# power_Exodia.net
KiCad netlist of a schematic drawn in EAGLE
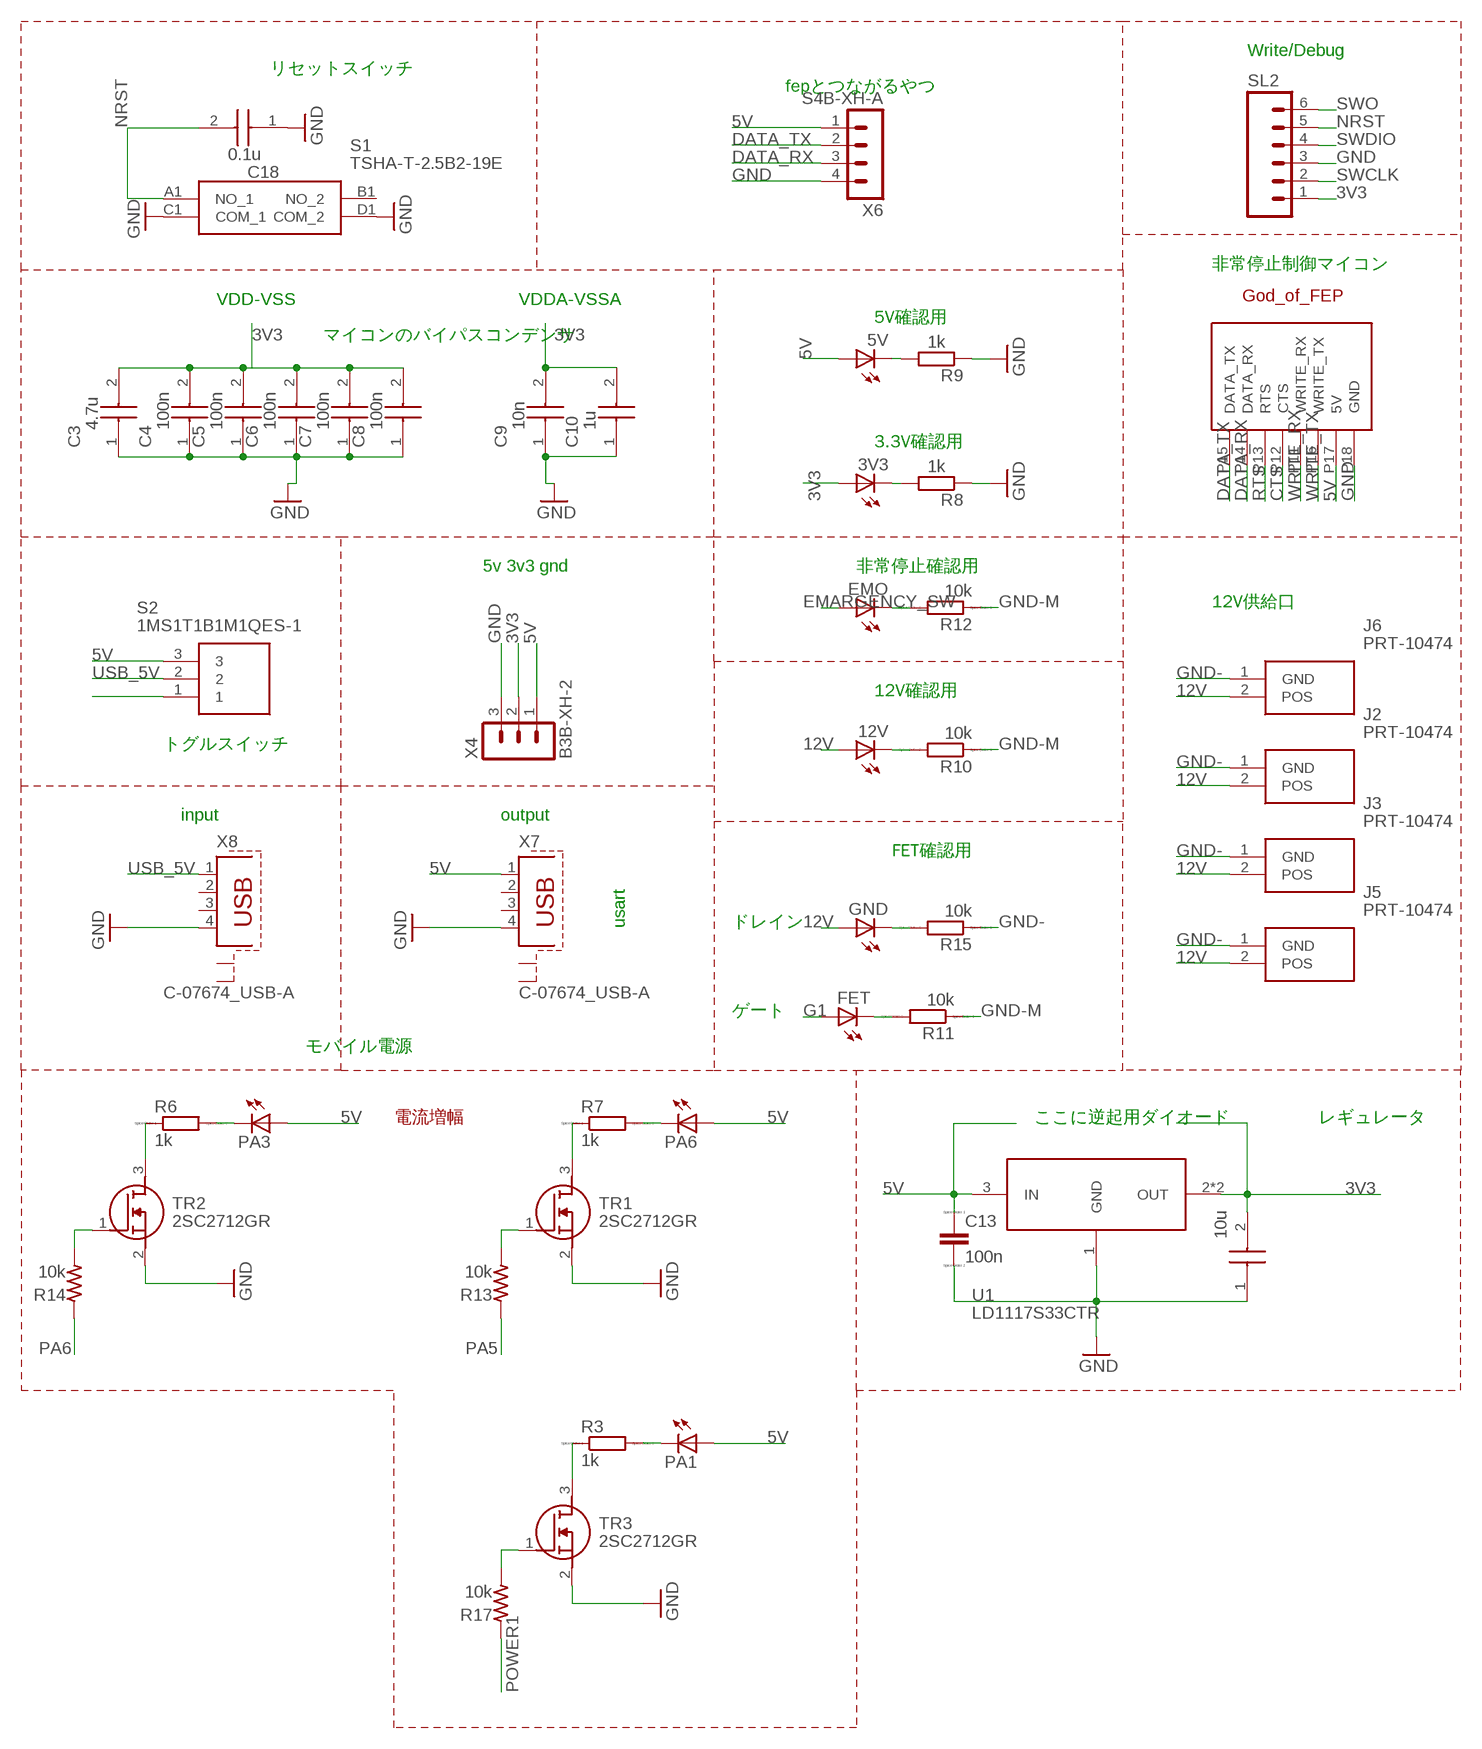
[diagram p0: schematic, sheet 1]
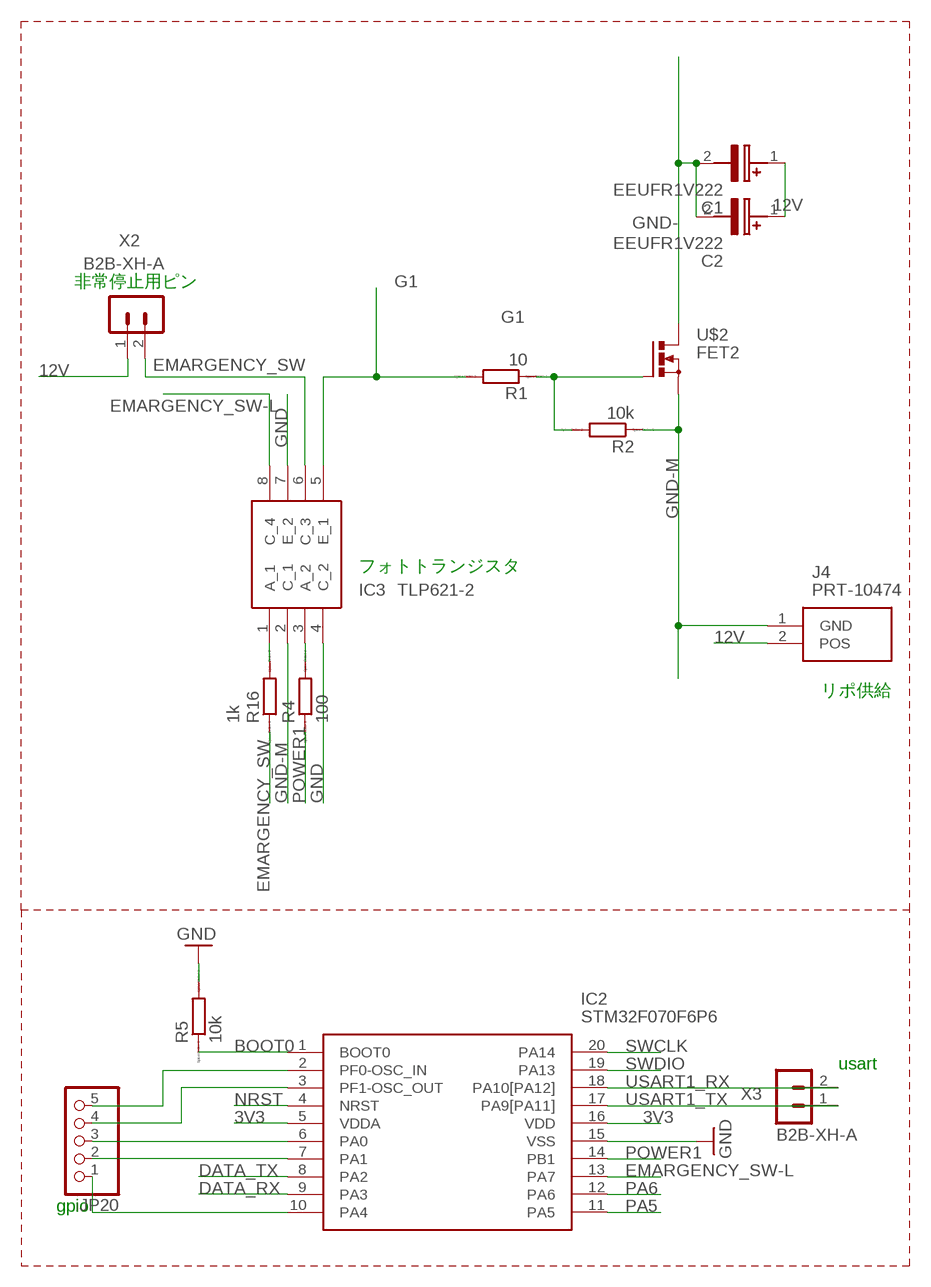
[diagram p1: schematic, sheet 2]

(export (version "E")
  (design (tool "Eeschema 10.0.6"))
  (components
    (comp (ref "3V3")
      (value "LED3MM")
      (footprint "eagle-import:LED3MM")
      (libsource (lib "eagle-import") (part "LED3MM"))
    )
    (comp (ref "5V")
      (value "LED3MM")
      (footprint "eagle-import:LED3MM")
      (libsource (lib "eagle-import") (part "LED3MM"))
    )
    (comp (ref "10U")
      (value "10u")
      (footprint "eagle-import:CAPC1608X90N")
      (fields
        (field (name "MANUFACTURER_PART_NUMBER") "GRM188B31A106KE69D")
        (field (name "RS_PART_NUMBER") "8847157P")
      )
      (libsource (lib "eagle-import") (part "GRM188B31A106KE69D"))
    )
    (comp (ref "12V")
      (value "LED3MM")
      (footprint "eagle-import:LED3MM")
      (libsource (lib "eagle-import") (part "LED3MM"))
    )
    (comp (ref "C3")
      (value "4.7u")
      (footprint "eagle-import:CAPC1709X100N")
      (fields
        (field (name "MANUFACTURER_PART_NUMBER") "AMK107BBJ476MA-RE")
        (field (name "MOUSER_PART_NUMBER") "963-AMK107BBJ476MARE")
        (field (name "RS_PART_NUMBER") "1843762P")
      )
      (libsource (lib "eagle-import") (part "AMK107BBJ476MA-RE"))
    )
    (comp (ref "C4")
      (value "100n")
      (footprint "eagle-import:CAPC1709X100N")
      (fields
        (field (name "MANUFACTURER_PART_NUMBER") "AMK107BBJ476MA-RE")
        (field (name "MOUSER_PART_NUMBER") "963-AMK107BBJ476MARE")
        (field (name "RS_PART_NUMBER") "1843762P")
      )
      (libsource (lib "eagle-import") (part "AMK107BBJ476MA-RE"))
    )
    (comp (ref "C5")
      (value "100n")
      (footprint "eagle-import:CAPC1709X100N")
      (fields
        (field (name "MANUFACTURER_PART_NUMBER") "AMK107BBJ476MA-RE")
        (field (name "MOUSER_PART_NUMBER") "963-AMK107BBJ476MARE")
        (field (name "RS_PART_NUMBER") "1843762P")
      )
      (libsource (lib "eagle-import") (part "AMK107BBJ476MA-RE"))
    )
    (comp (ref "C6")
      (value "100n")
      (footprint "eagle-import:CAPC1709X100N")
      (fields
        (field (name "MANUFACTURER_PART_NUMBER") "AMK107BBJ476MA-RE")
        (field (name "MOUSER_PART_NUMBER") "963-AMK107BBJ476MARE")
        (field (name "RS_PART_NUMBER") "1843762P")
      )
      (libsource (lib "eagle-import") (part "AMK107BBJ476MA-RE"))
    )
    (comp (ref "C7")
      (value "100n")
      (footprint "eagle-import:CAPC1709X100N")
      (fields
        (field (name "MANUFACTURER_PART_NUMBER") "AMK107BBJ476MA-RE")
        (field (name "MOUSER_PART_NUMBER") "963-AMK107BBJ476MARE")
        (field (name "RS_PART_NUMBER") "1843762P")
      )
      (libsource (lib "eagle-import") (part "AMK107BBJ476MA-RE"))
    )
    (comp (ref "C8")
      (value "100n")
      (footprint "eagle-import:CAPC1709X100N")
      (fields
        (field (name "MANUFACTURER_PART_NUMBER") "AMK107BBJ476MA-RE")
        (field (name "MOUSER_PART_NUMBER") "963-AMK107BBJ476MARE")
        (field (name "RS_PART_NUMBER") "1843762P")
      )
      (libsource (lib "eagle-import") (part "AMK107BBJ476MA-RE"))
    )
    (comp (ref "C9")
      (value "10n")
      (footprint "eagle-import:CAPC1709X100N")
      (fields
        (field (name "MANUFACTURER_PART_NUMBER") "AMK107BBJ476MA-RE")
        (field (name "MOUSER_PART_NUMBER") "963-AMK107BBJ476MARE")
        (field (name "RS_PART_NUMBER") "1843762P")
      )
      (libsource (lib "eagle-import") (part "AMK107BBJ476MA-RE"))
    )
    (comp (ref "C10")
      (value "1u")
      (footprint "eagle-import:CAPC1709X100N")
      (fields
        (field (name "MANUFACTURER_PART_NUMBER") "AMK107BBJ476MA-RE")
        (field (name "MOUSER_PART_NUMBER") "963-AMK107BBJ476MARE")
        (field (name "RS_PART_NUMBER") "1843762P")
      )
      (libsource (lib "eagle-import") (part "AMK107BBJ476MA-RE"))
    )
    (comp (ref "C13")
      (value "100n")
      (footprint "eagle-import:C1608")
      (libsource (lib "eagle-import") (part "CC1608"))
    )
    (comp (ref "C18")
      (value "0.1u")
      (footprint "eagle-import:CAPC1709X100N")
      (fields
        (field (name "MANUFACTURER_PART_NUMBER") "AMK107BBJ476MA-RE")
        (field (name "MOUSER_PART_NUMBER") "963-AMK107BBJ476MARE")
        (field (name "RS_PART_NUMBER") "1843762P")
      )
      (libsource (lib "eagle-import") (part "AMK107BBJ476MA-RE"))
    )
    (comp (ref "EMO")
      (value "LED3MM")
      (footprint "eagle-import:LED3MM")
      (libsource (lib "eagle-import") (part "LED3MM"))
    )
    (comp (ref "FEP_2")
      (value "GOD_OF_FEP")
      (footprint "eagle-import:GOD_OF_FEP")
      (libsource (lib "eagle-import") (part "GOD_OF_FEP"))
    )
    (comp (ref "FET")
      (value "LED3MM")
      (footprint "eagle-import:LED3MM")
      (libsource (lib "eagle-import") (part "LED3MM"))
    )
    (comp (ref "GND")
      (value "LED3MM")
      (footprint "eagle-import:LED3MM")
      (libsource (lib "eagle-import") (part "LED3MM"))
    )
    (comp (ref "J2")
      (value "PRT-10474")
      (footprint "eagle-import:SHDR2W320P716_1X2_1574X813X158")
      (fields (field (name "MOUSER_PART_NUMBER") "474-PRT-10474"))
      (libsource (lib "eagle-import") (part "PRT-10474"))
    )
    (comp (ref "J3")
      (value "PRT-10474")
      (footprint "eagle-import:SHDR2W320P716_1X2_1574X813X158")
      (fields (field (name "MOUSER_PART_NUMBER") "474-PRT-10474"))
      (libsource (lib "eagle-import") (part "PRT-10474"))
    )
    (comp (ref "J5")
      (value "PRT-10474")
      (footprint "eagle-import:SHDR2W320P716_1X2_1574X813X158")
      (fields (field (name "MOUSER_PART_NUMBER") "474-PRT-10474"))
      (libsource (lib "eagle-import") (part "PRT-10474"))
    )
    (comp (ref "J6")
      (value "PRT-10474")
      (footprint "eagle-import:SHDR2W320P716_1X2_1574X813X158")
      (fields (field (name "MOUSER_PART_NUMBER") "474-PRT-10474"))
      (libsource (lib "eagle-import") (part "PRT-10474"))
    )
    (comp (ref "PA1")
      (value "LED3MM")
      (footprint "eagle-import:LED3MM")
      (libsource (lib "eagle-import") (part "LED3MM"))
    )
    (comp (ref "PA3")
      (value "LED3MM")
      (footprint "eagle-import:LED3MM")
      (libsource (lib "eagle-import") (part "LED3MM"))
    )
    (comp (ref "PA6")
      (value "LED3MM")
      (footprint "eagle-import:LED3MM")
      (libsource (lib "eagle-import") (part "LED3MM"))
    )
    (comp (ref "R3")
      (value "1k")
      (footprint "eagle-import:R0603")
      (libsource (lib "eagle-import") (part "RR0603"))
    )
    (comp (ref "R6")
      (value "1k")
      (footprint "eagle-import:R0603")
      (libsource (lib "eagle-import") (part "RR0603"))
    )
    (comp (ref "R7")
      (value "1k")
      (footprint "eagle-import:R0603")
      (libsource (lib "eagle-import") (part "RR0603"))
    )
    (comp (ref "R8")
      (value "1k")
      (footprint "eagle-import:1608")
      (libsource (lib "eagle-import") (part "R1608"))
    )
    (comp (ref "R9")
      (value "1k")
      (footprint "eagle-import:1608")
      (libsource (lib "eagle-import") (part "R1608"))
    )
    (comp (ref "R10")
      (value "10k")
      (footprint "eagle-import:R0603")
      (libsource (lib "eagle-import") (part "RR0603"))
    )
    (comp (ref "R11")
      (value "10k")
      (footprint "eagle-import:R0603")
      (libsource (lib "eagle-import") (part "RR0603"))
    )
    (comp (ref "R12")
      (value "10k")
      (footprint "eagle-import:R0603")
      (libsource (lib "eagle-import") (part "RR0603"))
    )
    (comp (ref "R13")
      (value "10k")
      (footprint "eagle-import:SMD1608")
      (libsource (lib "eagle-import") (part "RESISTOR-US1608"))
    )
    (comp (ref "R14")
      (value "10k")
      (footprint "eagle-import:SMD1608")
      (libsource (lib "eagle-import") (part "RESISTOR-US1608"))
    )
    (comp (ref "R15")
      (value "10k")
      (footprint "eagle-import:R0603")
      (libsource (lib "eagle-import") (part "RR0603"))
    )
    (comp (ref "R17")
      (value "10k")
      (footprint "eagle-import:SMD1608")
      (libsource (lib "eagle-import") (part "RESISTOR-US1608"))
    )
    (comp (ref "S1")
      (value "TSHA-T-2.5B2-19E")
      (footprint "eagle-import:TSHAT25B219E")
      (libsource (lib "eagle-import") (part "TSHA-T-2.5B2-19E"))
    )
    (comp (ref "S2")
      (value "1MS1T1B1M1QES-1")
      (footprint "eagle-import:1MS1T1B1M1QES-1")
      (libsource (lib "eagle-import") (part "1MS1T1B1M1QES-1"))
    )
    (comp (ref "SL2")
      (value "MA06")
      (footprint "eagle-import:06PA")
      (libsource (lib "eagle-import") (part "MA06"))
    )
    (comp (ref "TR1")
      (value "2SC2712GR")
      (footprint "eagle-import:SOT-23")
      (libsource (lib "eagle-import") (part "SOT-23_NMOS"))
    )
    (comp (ref "TR2")
      (value "2SC2712GR")
      (footprint "eagle-import:SOT-23")
      (libsource (lib "eagle-import") (part "SOT-23_NMOS"))
    )
    (comp (ref "TR3")
      (value "2SC2712GR")
      (footprint "eagle-import:SOT-23")
      (libsource (lib "eagle-import") (part "SOT-23_NMOS"))
    )
    (comp (ref "U1")
      (value "LD1117S33CTR")
      (footprint "eagle-import:SOT223")
      (fields (field (name "MF") "STMicroelectronics"))
      (libsource (lib "eagle-import") (part "LD1117S33CTR"))
    )
    (comp (ref "X4")
      (value "B3B-XH-2")
      (footprint "eagle-import:B3B-XH-A")
      (libsource (lib "eagle-import") (part "B3B-XH-2"))
    )
    (comp (ref "X6")
      (value "S4B-XH-A")
      (footprint "eagle-import:S4B-XH-A")
      (libsource (lib "eagle-import") (part "S4B-XH-A"))
    )
    (comp (ref "X7")
      (value "C-07674_USB-A")
      (footprint "eagle-import:PN87520-S")
      (libsource (lib "eagle-import") (part "C-07674_USB-A"))
    )
    (comp (ref "X8")
      (value "C-07674_USB-A")
      (footprint "eagle-import:PN87520-S")
      (libsource (lib "eagle-import") (part "C-07674_USB-A"))
    )
    (comp (ref "C1")
      (value "EEUFR1V222")
      (footprint "eagle-import:CAPPRD750W85D1600H2700")
      (libsource (lib "eagle-import") (part "EEUFR1V222"))
    )
    (comp (ref "C2")
      (value "EEUFR1V222")
      (footprint "eagle-import:CAPPRD750W85D1600H2700")
      (libsource (lib "eagle-import") (part "EEUFR1V222"))
    )
    (comp (ref "IC2")
      (value "STM32F070F6P6")
      (footprint "eagle-import:SOP65P640X120-20N")
      (fields (field (name "MOUSER_PART_NUMBER") "511-STM32F070F6P6"))
      (libsource (lib "eagle-import") (part "STM32F070F6P6"))
    )
    (comp (ref "IC3")
      (value "TLP621-2")
      (footprint "eagle-import:DIP762W60P254L966H485Q8N")
      (fields (field (name "MOUSER_PART_NUMBER") "757-TLP621-2"))
      (libsource (lib "eagle-import") (part "TLP621-2"))
    )
    (comp (ref "J4")
      (value "PRT-10474")
      (footprint "eagle-import:SHDR2W320P716_1X2_1574X813X158")
      (fields (field (name "MOUSER_PART_NUMBER") "474-PRT-10474"))
      (libsource (lib "eagle-import") (part "PRT-10474"))
    )
    (comp (ref "JP20")
      (value "PINHD-1X5")
      (footprint "eagle-import:1X05")
      (libsource (lib "eagle-import") (part "PINHD-1X5"))
    )
    (comp (ref "R1")
      (value "10")
      (footprint "eagle-import:R0603")
      (libsource (lib "eagle-import") (part "RR0603"))
    )
    (comp (ref "R2")
      (value "10k")
      (footprint "eagle-import:R0603")
      (libsource (lib "eagle-import") (part "RR0603"))
    )
    (comp (ref "R4")
      (value "100")
      (footprint "eagle-import:R0603")
      (libsource (lib "eagle-import") (part "RR0603"))
    )
    (comp (ref "R5")
      (value "10k")
      (footprint "eagle-import:R0603")
      (libsource (lib "eagle-import") (part "RR0603"))
    )
    (comp (ref "R16")
      (value "1k")
      (footprint "eagle-import:R0603")
      (libsource (lib "eagle-import") (part "RR0603"))
    )
    (comp (ref "U$2")
      (value "FET2")
      (footprint "eagle-import:FET2")
      (libsource (lib "eagle-import") (part "FET2"))
    )
    (comp (ref "X2")
      (value "B2B-XH-A")
      (footprint "eagle-import:B2B-XH-A")
      (libsource (lib "eagle-import") (part "B2B-XH-A"))
    )
    (comp (ref "X3")
      (value "B2B-XH-A")
      (footprint "eagle-import:B2B-XH-A")
      (libsource (lib "eagle-import") (part "B2B-XH-A"))
    )
  )
  (nets
    (net (code "1") (name "3V3") (class "Default")
      (node (ref "10U") (pin "2") (pinfunction "2_2") (pintype "bidirectional"))
      (node (ref "3V3") (pin "A") (pinfunction "A_A") (pintype "passive"))
      (node (ref "C10") (pin "2") (pinfunction "2_2") (pintype "bidirectional"))
      (node (ref "C3") (pin "2") (pinfunction "2_2") (pintype "bidirectional"))
      (node (ref "C4") (pin "2") (pinfunction "2_2") (pintype "bidirectional"))
      (node (ref "C5") (pin "2") (pinfunction "2_2") (pintype "bidirectional"))
      (node (ref "C6") (pin "2") (pinfunction "2_2") (pintype "bidirectional"))
      (node (ref "C7") (pin "2") (pinfunction "2_2") (pintype "bidirectional"))
      (node (ref "C8") (pin "2") (pinfunction "2_2") (pintype "bidirectional"))
      (node (ref "C9") (pin "2") (pinfunction "2_2") (pintype "bidirectional"))
      (node (ref "IC2") (pin "16") (pinfunction "VDD_16") (pintype "bidirectional"))
      (node (ref "IC2") (pin "5") (pinfunction "VDDA_5") (pintype "bidirectional"))
      (node (ref "SL2") (pin "1") (pinfunction "1_1") (pintype "passive"))
      (node (ref "U1") (pin "2") (pinfunction "OUT_2") (pintype "output"))
      (node (ref "U1") (pin "4") (pinfunction "OUT_4") (pintype "output"))
      (node (ref "X4") (pin "2") (pinfunction "2_2") (pintype "passive"))
    )
    (net (code "2") (name "5V") (class "Default")
      (node (ref "5V") (pin "A") (pinfunction "A_A") (pintype "passive"))
      (node (ref "C13") (pin "1") (pinfunction "1_1") (pintype "passive"))
      (node (ref "FEP_2") (pin "P17") (pinfunction "5V_P17") (pintype "bidirectional"))
      (node (ref "PA1") (pin "A") (pinfunction "A_A") (pintype "passive"))
      (node (ref "PA3") (pin "A") (pinfunction "A_A") (pintype "passive"))
      (node (ref "PA6") (pin "A") (pinfunction "A_A") (pintype "passive"))
      (node (ref "S2") (pin "3") (pinfunction "3_3") (pintype "bidirectional"))
      (node (ref "U1") (pin "3") (pinfunction "IN_3") (pintype "input"))
      (node (ref "X4") (pin "1") (pinfunction "1_1") (pintype "passive"))
      (node (ref "X6") (pin "1") (pinfunction "1_1") (pintype "passive"))
      (node (ref "X7") (pin "1") (pinfunction "1_1") (pintype "passive"))
    )
    (net (code "3") (name "12V") (class "Default")
      (node (ref "12V") (pin "A") (pinfunction "A_A") (pintype "passive"))
      (node (ref "C1") (pin "1") (pinfunction "+_1") (pintype "bidirectional"))
      (node (ref "C2") (pin "1") (pinfunction "+_1") (pintype "bidirectional"))
      (node (ref "GND") (pin "A") (pinfunction "A_A") (pintype "passive"))
      (node (ref "J2") (pin "2") (pinfunction "POS_2") (pintype "power_in"))
      (node (ref "J3") (pin "2") (pinfunction "POS_2") (pintype "power_in"))
      (node (ref "J4") (pin "2") (pinfunction "POS_2") (pintype "power_in"))
      (node (ref "J5") (pin "2") (pinfunction "POS_2") (pintype "power_in"))
      (node (ref "J6") (pin "2") (pinfunction "POS_2") (pintype "power_in"))
      (node (ref "X2") (pin "1") (pinfunction "1_1") (pintype "passive"))
    )
    (net (code "4") (name "BOOT0") (class "Default")
      (node (ref "IC2") (pin "1") (pinfunction "BOOT0_1") (pintype "bidirectional"))
      (node (ref "R5") (pin "1") (pinfunction "1_1") (pintype "passive"))
    )
    (net (code "5") (name "CTS") (class "Default")
      (node (ref "FEP_2") (pin "P12") (pinfunction "CTS_P12") (pintype "bidirectional"))
    )
    (net (code "6") (name "DATA_RX") (class "Default")
      (node (ref "FEP_2") (pin "P14") (pinfunction "DATA_RX_P14") (pintype "bidirectional"))
      (node (ref "IC2") (pin "9") (pinfunction "PA3_9") (pintype "bidirectional"))
      (node (ref "X6") (pin "3") (pinfunction "3_3") (pintype "passive"))
    )
    (net (code "7") (name "DATA_TX") (class "Default")
      (node (ref "FEP_2") (pin "P15") (pinfunction "DATA_TX_P15") (pintype "bidirectional"))
      (node (ref "IC2") (pin "8") (pinfunction "PA2_8") (pintype "bidirectional"))
      (node (ref "X6") (pin "2") (pinfunction "2_2") (pintype "passive"))
    )
    (net (code "8") (name "EMARGENCY_SW") (class "Default")
      (node (ref "EMO") (pin "A") (pinfunction "A_A") (pintype "passive"))
      (node (ref "IC3") (pin "6") (pinfunction "C_3_6") (pintype "bidirectional"))
      (node (ref "R16") (pin "1") (pinfunction "1_1") (pintype "passive"))
      (node (ref "X2") (pin "2") (pinfunction "2_2") (pintype "passive"))
    )
    (net (code "9") (name "EMARGENCY_SW-L") (class "Default")
      (node (ref "IC2") (pin "13") (pinfunction "PA7_13") (pintype "bidirectional"))
      (node (ref "IC3") (pin "8") (pinfunction "C_4_8") (pintype "bidirectional"))
    )
    (net (code "10") (name "G1") (class "Default")
      (node (ref "FET") (pin "A") (pinfunction "A_A") (pintype "passive"))
      (node (ref "IC3") (pin "5") (pinfunction "E_1_5") (pintype "bidirectional"))
      (node (ref "R1") (pin "2") (pinfunction "2_2") (pintype "passive"))
    )
    (net (code "11") (name "GND") (class "Default")
      (node (ref "10U") (pin "1") (pinfunction "1_1") (pintype "bidirectional"))
      (node (ref "C10") (pin "1") (pinfunction "1_1") (pintype "bidirectional"))
      (node (ref "C13") (pin "2") (pinfunction "2_2") (pintype "passive"))
      (node (ref "C18") (pin "1") (pinfunction "1_1") (pintype "bidirectional"))
      (node (ref "C3") (pin "1") (pinfunction "1_1") (pintype "bidirectional"))
      (node (ref "C4") (pin "1") (pinfunction "1_1") (pintype "bidirectional"))
      (node (ref "C5") (pin "1") (pinfunction "1_1") (pintype "bidirectional"))
      (node (ref "C6") (pin "1") (pinfunction "1_1") (pintype "bidirectional"))
      (node (ref "C7") (pin "1") (pinfunction "1_1") (pintype "bidirectional"))
      (node (ref "C8") (pin "1") (pinfunction "1_1") (pintype "bidirectional"))
      (node (ref "C9") (pin "1") (pinfunction "1_1") (pintype "bidirectional"))
      (node (ref "FEP_2") (pin "P18") (pinfunction "GND_P18") (pintype "bidirectional"))
      (node (ref "IC2") (pin "15") (pinfunction "VSS_15") (pintype "bidirectional"))
      (node (ref "IC3") (pin "4") (pinfunction "C_2_4") (pintype "bidirectional"))
      (node (ref "IC3") (pin "7") (pinfunction "E_2_7") (pintype "bidirectional"))
      (node (ref "R5") (pin "2") (pinfunction "2_2") (pintype "passive"))
      (node (ref "R8") (pin "1") (pinfunction "1_1") (pintype "passive"))
      (node (ref "R9") (pin "1") (pinfunction "1_1") (pintype "passive"))
      (node (ref "S1") (pin "C1") (pinfunction "COM_1_C1") (pintype "bidirectional"))
      (node (ref "S1") (pin "D1") (pinfunction "COM_2_D1") (pintype "bidirectional"))
      (node (ref "SL2") (pin "3") (pinfunction "3_3") (pintype "passive"))
      (node (ref "TR1") (pin "2") (pinfunction "S_2") (pintype "bidirectional"))
      (node (ref "TR2") (pin "2") (pinfunction "S_2") (pintype "bidirectional"))
      (node (ref "TR3") (pin "2") (pinfunction "S_2") (pintype "bidirectional"))
      (node (ref "U1") (pin "1") (pinfunction "GND_1") (pintype "passive"))
      (node (ref "X4") (pin "3") (pinfunction "3_3") (pintype "passive"))
      (node (ref "X6") (pin "4") (pinfunction "4_4") (pintype "passive"))
      (node (ref "X7") (pin "4") (pinfunction "4_4") (pintype "passive"))
      (node (ref "X8") (pin "4") (pinfunction "4_4") (pintype "passive"))
    )
    (net (code "12") (name "GND-") (class "Default")
      (node (ref "C1") (pin "2") (pinfunction "-_2") (pintype "bidirectional"))
      (node (ref "C2") (pin "2") (pinfunction "-_2") (pintype "bidirectional"))
      (node (ref "J2") (pin "1") (pinfunction "GND_1") (pintype "power_in"))
      (node (ref "J3") (pin "1") (pinfunction "GND_1") (pintype "power_in"))
      (node (ref "J5") (pin "1") (pinfunction "GND_1") (pintype "power_in"))
      (node (ref "J6") (pin "1") (pinfunction "GND_1") (pintype "power_in"))
      (node (ref "R15") (pin "1") (pinfunction "1_1") (pintype "passive"))
      (node (ref "U$2") (pin "D") (pinfunction "D_D") (pintype "passive"))
    )
    (net (code "13") (name "GND-M") (class "Default")
      (node (ref "IC3") (pin "2") (pinfunction "C_1_2") (pintype "bidirectional"))
      (node (ref "J4") (pin "1") (pinfunction "GND_1") (pintype "power_in"))
      (node (ref "R10") (pin "1") (pinfunction "1_1") (pintype "passive"))
      (node (ref "R11") (pin "1") (pinfunction "1_1") (pintype "passive"))
      (node (ref "R12") (pin "1") (pinfunction "1_1") (pintype "passive"))
      (node (ref "R2") (pin "1") (pinfunction "1_1") (pintype "passive"))
      (node (ref "U$2") (pin "S") (pinfunction "S_S") (pintype "passive"))
    )
    (net (code "14") (name "NRST") (class "Default")
      (node (ref "C18") (pin "2") (pinfunction "2_2") (pintype "bidirectional"))
      (node (ref "IC2") (pin "4") (pinfunction "NRST_4") (pintype "bidirectional"))
      (node (ref "S1") (pin "A1") (pinfunction "NO_1_A1") (pintype "bidirectional"))
      (node (ref "SL2") (pin "5") (pinfunction "5_5") (pintype "passive"))
    )
    (net (code "15") (name "Net-(3V3-C)") (class "Default")
      (node (ref "3V3") (pin "K") (pinfunction "C_K") (pintype "passive"))
      (node (ref "R8") (pin "2") (pinfunction "2_2") (pintype "passive"))
    )
    (net (code "16") (name "Net-(5V-C)") (class "Default")
      (node (ref "5V") (pin "K") (pinfunction "C_K") (pintype "passive"))
      (node (ref "R9") (pin "2") (pinfunction "2_2") (pintype "passive"))
    )
    (net (code "17") (name "Net-(12V-C)") (class "Default")
      (node (ref "12V") (pin "K") (pinfunction "C_K") (pintype "passive"))
      (node (ref "R10") (pin "2") (pinfunction "2_2") (pintype "passive"))
    )
    (net (code "18") (name "Net-(EMO-C)") (class "Default")
      (node (ref "EMO") (pin "K") (pinfunction "C_K") (pintype "passive"))
      (node (ref "R12") (pin "2") (pinfunction "2_2") (pintype "passive"))
    )
    (net (code "19") (name "Net-(FET-C)") (class "Default")
      (node (ref "FET") (pin "K") (pinfunction "C_K") (pintype "passive"))
      (node (ref "R11") (pin "2") (pinfunction "2_2") (pintype "passive"))
    )
    (net (code "20") (name "Net-(GND-C)") (class "Default")
      (node (ref "GND") (pin "K") (pinfunction "C_K") (pintype "passive"))
      (node (ref "R15") (pin "2") (pinfunction "2_2") (pintype "passive"))
    )
    (net (code "21") (name "Net-(IC2-PA0)") (class "Default")
      (node (ref "IC2") (pin "6") (pinfunction "PA0_6") (pintype "bidirectional"))
      (node (ref "JP20") (pin "3") (pinfunction "3_3") (pintype "passive"))
    )
    (net (code "22") (name "Net-(IC2-PA1)") (class "Default")
      (node (ref "IC2") (pin "7") (pinfunction "PA1_7") (pintype "bidirectional"))
      (node (ref "JP20") (pin "2") (pinfunction "2_2") (pintype "passive"))
    )
    (net (code "23") (name "Net-(IC2-PA4)") (class "Default")
      (node (ref "IC2") (pin "10") (pinfunction "PA4_10") (pintype "bidirectional"))
      (node (ref "JP20") (pin "1") (pinfunction "1_1") (pintype "passive"))
    )
    (net (code "24") (name "Net-(IC2-PF0-OSC_IN)") (class "Default")
      (node (ref "IC2") (pin "2") (pinfunction "PF0-OSC_IN_2") (pintype "bidirectional"))
      (node (ref "JP20") (pin "5") (pinfunction "5_5") (pintype "passive"))
    )
    (net (code "25") (name "Net-(IC2-PF1-OSC_OUT)") (class "Default")
      (node (ref "IC2") (pin "3") (pinfunction "PF1-OSC_OUT_3") (pintype "bidirectional"))
      (node (ref "JP20") (pin "4") (pinfunction "4_4") (pintype "passive"))
    )
    (net (code "26") (name "Net-(IC3-A_1)") (class "Default")
      (node (ref "IC3") (pin "1") (pinfunction "A_1_1") (pintype "bidirectional"))
      (node (ref "R16") (pin "2") (pinfunction "2_2") (pintype "passive"))
    )
    (net (code "27") (name "Net-(IC3-A_2)") (class "Default")
      (node (ref "IC3") (pin "3") (pinfunction "A_2_3") (pintype "bidirectional"))
      (node (ref "R4") (pin "2") (pinfunction "2_2") (pintype "passive"))
    )
    (net (code "28") (name "Net-(PA1-C)") (class "Default")
      (node (ref "PA1") (pin "K") (pinfunction "C_K") (pintype "passive"))
      (node (ref "R3") (pin "2") (pinfunction "2_2") (pintype "passive"))
    )
    (net (code "29") (name "Net-(PA3-C)") (class "Default")
      (node (ref "PA3") (pin "K") (pinfunction "C_K") (pintype "passive"))
      (node (ref "R6") (pin "2") (pinfunction "2_2") (pintype "passive"))
    )
    (net (code "30") (name "Net-(PA6-C)") (class "Default")
      (node (ref "PA6") (pin "K") (pinfunction "C_K") (pintype "passive"))
      (node (ref "R7") (pin "2") (pinfunction "2_2") (pintype "passive"))
    )
    (net (code "31") (name "Net-(R1-Pad1)") (class "Default")
      (node (ref "R1") (pin "1") (pinfunction "1_1") (pintype "passive"))
      (node (ref "R2") (pin "2") (pinfunction "2_2") (pintype "passive"))
      (node (ref "U$2") (pin "G") (pinfunction "G_G") (pintype "passive"))
    )
    (net (code "32") (name "Net-(TR1-D)") (class "Default")
      (node (ref "R7") (pin "1") (pinfunction "1_1") (pintype "passive"))
      (node (ref "TR1") (pin "3") (pinfunction "D_3") (pintype "bidirectional"))
    )
    (net (code "33") (name "Net-(TR1-G)") (class "Default")
      (node (ref "R13") (pin "2") (pinfunction "2_2") (pintype "passive"))
      (node (ref "TR1") (pin "1") (pinfunction "G_1") (pintype "bidirectional"))
    )
    (net (code "34") (name "Net-(TR2-D)") (class "Default")
      (node (ref "R6") (pin "1") (pinfunction "1_1") (pintype "passive"))
      (node (ref "TR2") (pin "3") (pinfunction "D_3") (pintype "bidirectional"))
    )
    (net (code "35") (name "Net-(TR2-G)") (class "Default")
      (node (ref "R14") (pin "2") (pinfunction "2_2") (pintype "passive"))
      (node (ref "TR2") (pin "1") (pinfunction "G_1") (pintype "bidirectional"))
    )
    (net (code "36") (name "Net-(TR3-D)") (class "Default")
      (node (ref "R3") (pin "1") (pinfunction "1_1") (pintype "passive"))
      (node (ref "TR3") (pin "3") (pinfunction "D_3") (pintype "bidirectional"))
    )
    (net (code "37") (name "Net-(TR3-G)") (class "Default")
      (node (ref "R17") (pin "2") (pinfunction "2_2") (pintype "passive"))
      (node (ref "TR3") (pin "1") (pinfunction "G_1") (pintype "bidirectional"))
    )
    (net (code "38") (name "PA5") (class "Default")
      (node (ref "IC2") (pin "11") (pinfunction "PA5_11") (pintype "bidirectional"))
      (node (ref "R13") (pin "1") (pinfunction "1_1") (pintype "passive"))
    )
    (net (code "39") (name "PA6") (class "Default")
      (node (ref "IC2") (pin "12") (pinfunction "PA6_12") (pintype "bidirectional"))
      (node (ref "R14") (pin "1") (pinfunction "1_1") (pintype "passive"))
    )
    (net (code "40") (name "POWER1") (class "Default")
      (node (ref "IC2") (pin "14") (pinfunction "PB1_14") (pintype "bidirectional"))
      (node (ref "R17") (pin "1") (pinfunction "1_1") (pintype "passive"))
      (node (ref "R4") (pin "1") (pinfunction "1_1") (pintype "passive"))
    )
    (net (code "41") (name "RTS") (class "Default")
      (node (ref "FEP_2") (pin "P13") (pinfunction "RTS_P13") (pintype "bidirectional"))
    )
    (net (code "42") (name "SWCLK") (class "Default")
      (node (ref "IC2") (pin "20") (pinfunction "PA14_20") (pintype "bidirectional"))
      (node (ref "SL2") (pin "2") (pinfunction "2_2") (pintype "passive"))
    )
    (net (code "43") (name "SWDIO") (class "Default")
      (node (ref "IC2") (pin "19") (pinfunction "PA13_19") (pintype "bidirectional"))
      (node (ref "SL2") (pin "4") (pinfunction "4_4") (pintype "passive"))
    )
    (net (code "44") (name "SWO") (class "Default")
      (node (ref "SL2") (pin "6") (pinfunction "6_6") (pintype "passive"))
    )
    (net (code "45") (name "USART1_RX") (class "Default")
      (node (ref "IC2") (pin "18") (pinfunction "PA10[PA12]_18") (pintype "bidirectional"))
      (node (ref "X3") (pin "2") (pinfunction "2_2") (pintype "passive"))
    )
    (net (code "46") (name "USART1_TX") (class "Default")
      (node (ref "IC2") (pin "17") (pinfunction "PA9[PA11]_17") (pintype "bidirectional"))
      (node (ref "X3") (pin "1") (pinfunction "1_1") (pintype "passive"))
    )
    (net (code "47") (name "USB_5V") (class "Default")
      (node (ref "S2") (pin "2") (pinfunction "2_2") (pintype "bidirectional"))
      (node (ref "X8") (pin "1") (pinfunction "1_1") (pintype "passive"))
    )
    (net (code "48") (name "WRITE_RX") (class "Default")
      (node (ref "FEP_2") (pin "P11") (pinfunction "WRITE_RX_P11") (pintype "bidirectional"))
    )
    (net (code "49") (name "WRITE_TX") (class "Default")
      (node (ref "FEP_2") (pin "P16") (pinfunction "WRITE_TX_P16") (pintype "bidirectional"))
    )
    (net (code "50") (name "unconnected-(S1-NO_2-PadB1)") (class "Default")
      (node (ref "S1") (pin "B1") (pinfunction "NO_2_B1") (pintype "bidirectional"))
    )
    (net (code "51") (name "unconnected-(S2-Pad1)") (class "Default")
      (node (ref "S2") (pin "1") (pinfunction "1_1") (pintype "bidirectional"))
    )
    (net (code "52") (name "unconnected-(X7-Pad2)") (class "Default")
      (node (ref "X7") (pin "2") (pinfunction "2_2") (pintype "passive"))
    )
    (net (code "53") (name "unconnected-(X7-Pad3)") (class "Default")
      (node (ref "X7") (pin "3") (pinfunction "3_3") (pintype "passive"))
    )
    (net (code "54") (name "unconnected-(X7-PadS1)") (class "Default")
      (node (ref "X7") (pin "S1") (pinfunction "S1_S1") (pintype "passive"))
    )
    (net (code "55") (name "unconnected-(X7-PadS2)") (class "Default")
      (node (ref "X7") (pin "S2") (pinfunction "S2_S2") (pintype "passive"))
    )
    (net (code "56") (name "unconnected-(X8-Pad2)") (class "Default")
      (node (ref "X8") (pin "2") (pinfunction "2_2") (pintype "passive"))
    )
    (net (code "57") (name "unconnected-(X8-Pad3)") (class "Default")
      (node (ref "X8") (pin "3") (pinfunction "3_3") (pintype "passive"))
    )
    (net (code "58") (name "unconnected-(X8-PadS1)") (class "Default")
      (node (ref "X8") (pin "S1") (pinfunction "S1_S1") (pintype "passive"))
    )
    (net (code "59") (name "unconnected-(X8-PadS2)") (class "Default")
      (node (ref "X8") (pin "S2") (pinfunction "S2_S2") (pintype "passive"))
    )
  )
)
